# H3_CPU_02.net
KiCad netlist of a schematic drawn in Altium Designer
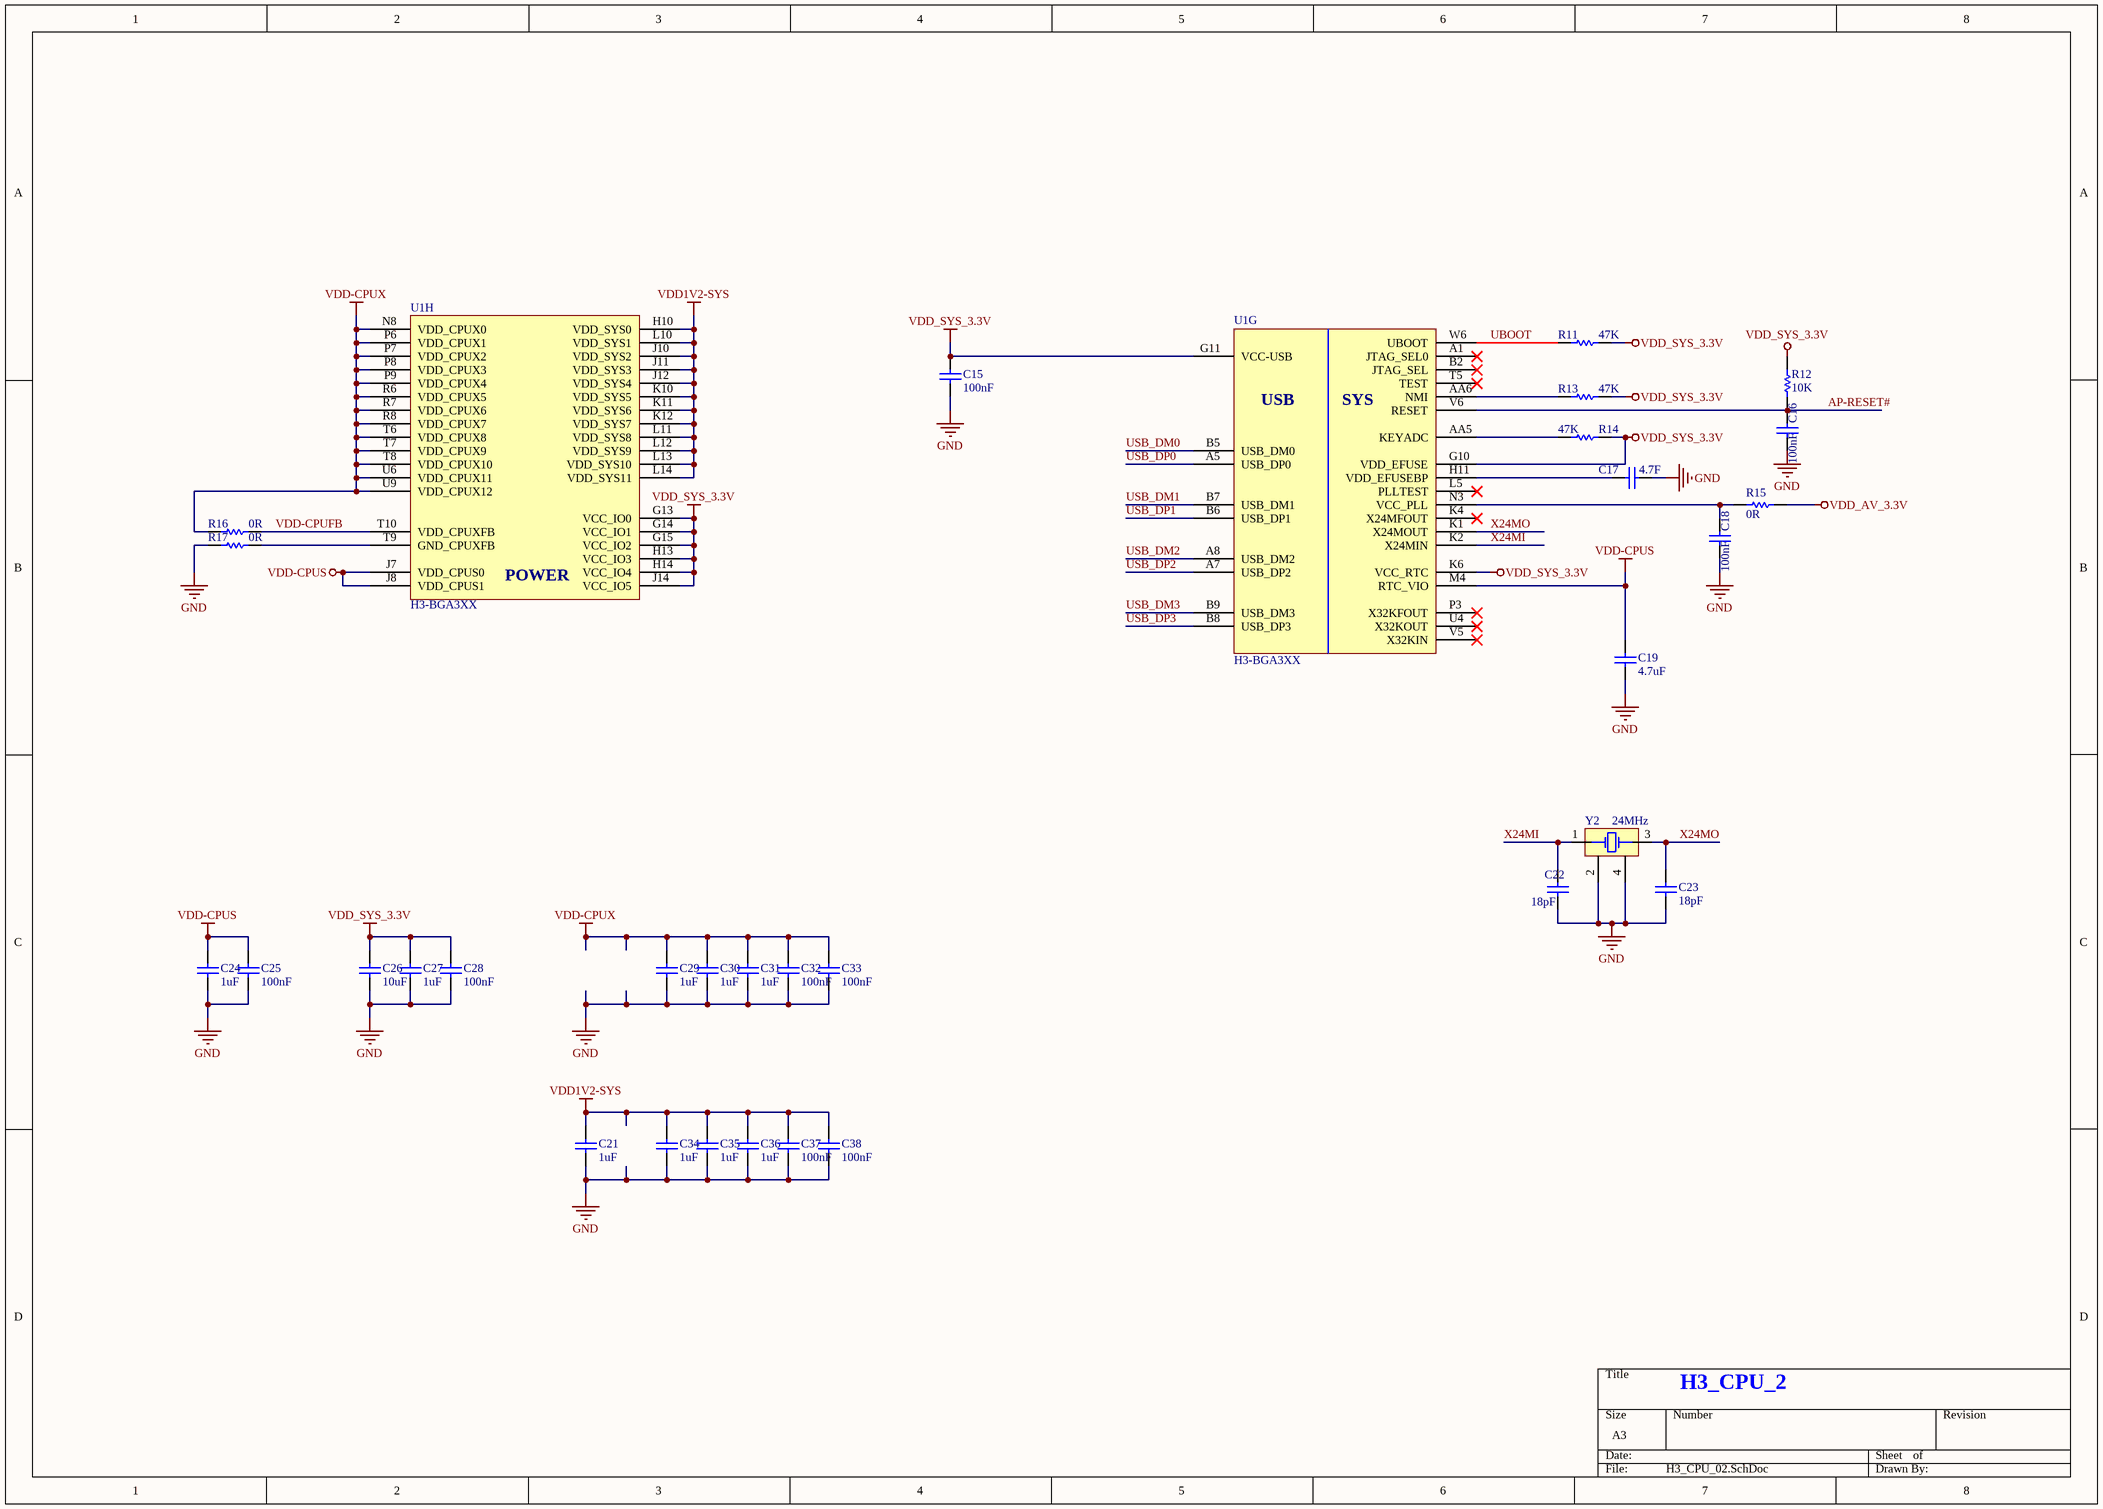
[diagram p0: H3_CPU_02.SchDoc]

(export (version "E")
  (design (tool "Eeschema 10.0.6"))
  (components
    (comp (ref "C15")
      (value "100nF")
      (footprint "H3_Core:C0402")
      (description "电容")
      (fields (field (name "PUBLISHER") "Altium Limited"))
      (libsource (lib "Devices") (part "C0402"))
    )
    (comp (ref "C16")
      (value "100nF")
      (footprint "H3_Core:C0402")
      (description "电容")
      (fields (field (name "PUBLISHER") "Altium Limited"))
      (libsource (lib "Devices") (part "C0402"))
    )
    (comp (ref "C17")
      (value "4.7F")
      (footprint "H3_Core:C0402")
      (description "电容")
      (fields (field (name "PUBLISHER") "Altium Limited"))
      (libsource (lib "Devices") (part "C0402"))
    )
    (comp (ref "C18")
      (value "100nF")
      (footprint "H3_Core:C0402")
      (description "电容")
      (fields (field (name "PUBLISHER") "Altium Limited"))
      (libsource (lib "Devices") (part "C0402"))
    )
    (comp (ref "C19")
      (value "4.7uF")
      (footprint "H3_Core:C0402")
      (description "电容")
      (fields (field (name "PUBLISHER") "Altium Limited"))
      (libsource (lib "Devices") (part "C0402"))
    )
    (comp (ref "C21")
      (value "1uF")
      (footprint "H3_Core:C0402")
      (description "电容")
      (fields (field (name "PUBLISHER") "Altium Limited"))
      (libsource (lib "Devices") (part "C0402"))
    )
    (comp (ref "C22")
      (value "18pF")
      (footprint "H3_Core:C0402")
      (description "电容")
      (fields (field (name "PUBLISHER") "Altium Limited"))
      (libsource (lib "Devices") (part "C0402"))
    )
    (comp (ref "C23")
      (value "18pF")
      (footprint "H3_Core:C0402")
      (description "电容")
      (fields (field (name "PUBLISHER") "Altium Limited"))
      (libsource (lib "Devices") (part "C0402"))
    )
    (comp (ref "C24")
      (value "1uF")
      (footprint "H3_Core:C0402")
      (description "电容")
      (fields (field (name "PUBLISHER") "Altium Limited"))
      (libsource (lib "Devices") (part "C0402"))
    )
    (comp (ref "C25")
      (value "100nF")
      (footprint "H3_Core:C0402")
      (description "电容")
      (fields (field (name "PUBLISHER") "Altium Limited"))
      (libsource (lib "Devices") (part "C0402"))
    )
    (comp (ref "C26")
      (value "10uF")
      (footprint "H3_Core:C0603")
      (description "电容")
      (fields (field (name "PUBLISHER") "Altium Limited"))
      (libsource (lib "Devices") (part "C0603"))
    )
    (comp (ref "C27")
      (value "1uF")
      (footprint "H3_Core:C0402")
      (description "电容")
      (fields (field (name "PUBLISHER") "Altium Limited"))
      (libsource (lib "Devices") (part "C0402"))
    )
    (comp (ref "C28")
      (value "100nF")
      (footprint "H3_Core:C0402")
      (description "电容")
      (fields (field (name "PUBLISHER") "Altium Limited"))
      (libsource (lib "Devices") (part "C0402"))
    )
    (comp (ref "C29")
      (value "1uF")
      (footprint "H3_Core:C0402")
      (description "电容")
      (fields (field (name "PUBLISHER") "Altium Limited"))
      (libsource (lib "Devices") (part "C0402"))
    )
    (comp (ref "C30")
      (value "1uF")
      (footprint "H3_Core:C0402")
      (description "电容")
      (fields (field (name "PUBLISHER") "Altium Limited"))
      (libsource (lib "Devices") (part "C0402"))
    )
    (comp (ref "C31")
      (value "1uF")
      (footprint "H3_Core:C0402")
      (description "电容")
      (fields (field (name "PUBLISHER") "Altium Limited"))
      (libsource (lib "Devices") (part "C0402"))
    )
    (comp (ref "C32")
      (value "100nF")
      (footprint "H3_Core:C0402")
      (description "电容")
      (fields (field (name "PUBLISHER") "Altium Limited"))
      (libsource (lib "Devices") (part "C0402"))
    )
    (comp (ref "C33")
      (value "100nF")
      (footprint "H3_Core:C0402")
      (description "电容")
      (fields (field (name "PUBLISHER") "Altium Limited"))
      (libsource (lib "Devices") (part "C0402"))
    )
    (comp (ref "C34")
      (value "1uF")
      (footprint "H3_Core:C0402")
      (description "电容")
      (fields (field (name "PUBLISHER") "Altium Limited"))
      (libsource (lib "Devices") (part "C0402"))
    )
    (comp (ref "C35")
      (value "1uF")
      (footprint "H3_Core:C0402")
      (description "电容")
      (fields (field (name "PUBLISHER") "Altium Limited"))
      (libsource (lib "Devices") (part "C0402"))
    )
    (comp (ref "C36")
      (value "1uF")
      (footprint "H3_Core:C0402")
      (description "电容")
      (fields (field (name "PUBLISHER") "Altium Limited"))
      (libsource (lib "Devices") (part "C0402"))
    )
    (comp (ref "C37")
      (value "100nF")
      (footprint "H3_Core:C0402")
      (description "电容")
      (fields (field (name "PUBLISHER") "Altium Limited"))
      (libsource (lib "Devices") (part "C0402"))
    )
    (comp (ref "C38")
      (value "100nF")
      (footprint "H3_Core:C0402")
      (description "电容")
      (fields (field (name "PUBLISHER") "Altium Limited"))
      (libsource (lib "Devices") (part "C0402"))
    )
    (comp (ref "R11")
      (value "47K")
      (footprint "H3_Core:R0402")
      (description "电阻")
      (fields (field (name "PUBLISHER") "Altium Limited"))
      (libsource (lib "Devices") (part "RES0402"))
    )
    (comp (ref "R12")
      (value "10K")
      (footprint "H3_Core:R0402")
      (description "电阻")
      (fields (field (name "PUBLISHER") "Altium Limited"))
      (libsource (lib "Devices") (part "RES0402"))
    )
    (comp (ref "R13")
      (value "47K")
      (footprint "H3_Core:R0402")
      (description "电阻")
      (fields (field (name "PUBLISHER") "Altium Limited"))
      (libsource (lib "Devices") (part "RES0402"))
    )
    (comp (ref "R14")
      (value "47K")
      (footprint "H3_Core:R0402")
      (description "电阻")
      (fields (field (name "PUBLISHER") "Altium Limited"))
      (libsource (lib "Devices") (part "RES0402"))
    )
    (comp (ref "R15")
      (value "0R")
      (footprint "H3_Core:R0402")
      (description "电阻")
      (fields (field (name "PUBLISHER") "Altium Limited"))
      (libsource (lib "Devices") (part "RES0402"))
    )
    (comp (ref "R16")
      (value "0R")
      (footprint "H3_Core:R0402")
      (description "电阻")
      (fields (field (name "PUBLISHER") "Altium Limited"))
      (libsource (lib "Devices") (part "RES0402"))
    )
    (comp (ref "R17")
      (value "0R")
      (footprint "H3_Core:R0402")
      (description "电阻")
      (fields (field (name "PUBLISHER") "Altium Limited"))
      (libsource (lib "Devices") (part "RES0402"))
    )
    (comp (ref "U1") (value "H3-BGA3XX") (footprint "BGA-H3-347") (libsource (lib "IC") (part "H3-BGA3XX")))
    (comp (ref "Y2")
      (value "24MHz")
      (footprint "H3_Core:X-TSX-3225")
      (description "Crystal Oscillator")
      (fields (field (name "PUBLISHER") "Altium Limited"))
      (libsource (lib "Devices") (part "XTAL_1"))
    )
  )
  (nets
    (net (code "1") (name "/AP-RESET#") (class "Default")
      (node (ref "C16") (pin "2") (pinfunction "2_2") (pintype "passive"))
      (node (ref "R12") (pin "1") (pinfunction "1_1") (pintype "passive"))
      (node (ref "U1") (pin "V6") (pinfunction "RESET_V6") (pintype "passive"))
    )
    (net (code "2") (name "/UBOOT") (class "Default")
      (node (ref "R11") (pin "2") (pinfunction "2_2") (pintype "passive"))
      (node (ref "U1") (pin "W6") (pinfunction "UBOOT_W6") (pintype "passive"))
    )
    (net (code "3") (name "/USB_DM0") (class "Default")
      (node (ref "U1") (pin "B5") (pinfunction "USB_DM0_B5") (pintype "passive"))
    )
    (net (code "4") (name "/USB_DM1") (class "Default")
      (node (ref "U1") (pin "B7") (pinfunction "USB_DM1_B7") (pintype "passive"))
    )
    (net (code "5") (name "/USB_DM2") (class "Default")
      (node (ref "U1") (pin "A8") (pinfunction "USB_DM2_A8") (pintype "passive"))
    )
    (net (code "6") (name "/USB_DM3") (class "Default")
      (node (ref "U1") (pin "B9") (pinfunction "USB_DM3_B9") (pintype "passive"))
    )
    (net (code "7") (name "/USB_DP0") (class "Default")
      (node (ref "U1") (pin "A5") (pinfunction "USB_DP0_A5") (pintype "passive"))
    )
    (net (code "8") (name "/USB_DP1") (class "Default")
      (node (ref "U1") (pin "B6") (pinfunction "USB_DP1_B6") (pintype "passive"))
    )
    (net (code "9") (name "/USB_DP2") (class "Default")
      (node (ref "U1") (pin "A7") (pinfunction "USB_DP2_A7") (pintype "passive"))
    )
    (net (code "10") (name "/USB_DP3") (class "Default")
      (node (ref "U1") (pin "B8") (pinfunction "USB_DP3_B8") (pintype "passive"))
    )
    (net (code "11") (name "/VDD-CPUFB") (class "Default")
      (node (ref "R16") (pin "1") (pinfunction "1_1") (pintype "passive"))
      (node (ref "U1") (pin "T10") (pinfunction "VDD_CPUXFB_T10") (pintype "passive"))
    )
    (net (code "12") (name "/X24MI") (class "Default")
      (node (ref "C22") (pin "2") (pinfunction "2_2") (pintype "passive"))
      (node (ref "U1") (pin "K2") (pinfunction "X24MIN_K2") (pintype "passive"))
      (node (ref "Y2") (pin "1") (pinfunction "1_1") (pintype "passive"))
    )
    (net (code "13") (name "/X24MO") (class "Default")
      (node (ref "C23") (pin "2") (pinfunction "2_2") (pintype "passive"))
      (node (ref "U1") (pin "K1") (pinfunction "X24MOUT_K1") (pintype "passive"))
      (node (ref "Y2") (pin "3") (pinfunction "3_3") (pintype "passive"))
    )
    (net (code "14") (name "GND") (class "Default")
      (node (ref "C15") (pin "1") (pinfunction "1_1") (pintype "passive"))
      (node (ref "C16") (pin "1") (pinfunction "1_1") (pintype "passive"))
      (node (ref "C17") (pin "1") (pinfunction "1_1") (pintype "passive"))
      (node (ref "C18") (pin "1") (pinfunction "1_1") (pintype "passive"))
      (node (ref "C19") (pin "1") (pinfunction "1_1") (pintype "passive"))
      (node (ref "C21") (pin "1") (pinfunction "1_1") (pintype "passive"))
      (node (ref "C22") (pin "1") (pinfunction "1_1") (pintype "passive"))
      (node (ref "C23") (pin "1") (pinfunction "1_1") (pintype "passive"))
      (node (ref "C24") (pin "1") (pinfunction "1_1") (pintype "passive"))
      (node (ref "C25") (pin "1") (pinfunction "1_1") (pintype "passive"))
      (node (ref "C26") (pin "1") (pinfunction "1_1") (pintype "passive"))
      (node (ref "C27") (pin "1") (pinfunction "1_1") (pintype "passive"))
      (node (ref "C28") (pin "1") (pinfunction "1_1") (pintype "passive"))
      (node (ref "C29") (pin "1") (pinfunction "1_1") (pintype "passive"))
      (node (ref "C30") (pin "1") (pinfunction "1_1") (pintype "passive"))
      (node (ref "C31") (pin "1") (pinfunction "1_1") (pintype "passive"))
      (node (ref "C32") (pin "1") (pinfunction "1_1") (pintype "passive"))
      (node (ref "C33") (pin "1") (pinfunction "1_1") (pintype "passive"))
      (node (ref "C34") (pin "1") (pinfunction "1_1") (pintype "passive"))
      (node (ref "C35") (pin "1") (pinfunction "1_1") (pintype "passive"))
      (node (ref "C36") (pin "1") (pinfunction "1_1") (pintype "passive"))
      (node (ref "C37") (pin "1") (pinfunction "1_1") (pintype "passive"))
      (node (ref "C38") (pin "1") (pinfunction "1_1") (pintype "passive"))
      (node (ref "R17") (pin "1") (pinfunction "1_1") (pintype "passive"))
      (node (ref "Y2") (pin "2") (pinfunction "2_2") (pintype "passive"))
      (node (ref "Y2") (pin "4") (pinfunction "4_4") (pintype "passive"))
    )
    (net (code "15") (name "Net-(U1G-KEYADC)") (class "Default")
      (node (ref "R14") (pin "1") (pinfunction "1_1") (pintype "passive"))
      (node (ref "U1") (pin "AA5") (pinfunction "KEYADC_AA5") (pintype "passive"))
    )
    (net (code "16") (name "Net-(U1G-NMI)") (class "Default")
      (node (ref "R13") (pin "1") (pinfunction "1_1") (pintype "passive"))
      (node (ref "U1") (pin "AA6") (pinfunction "NMI_AA6") (pintype "passive"))
    )
    (net (code "17") (name "Net-(U1G-VCC_PLL)") (class "Default")
      (node (ref "C18") (pin "2") (pinfunction "2_2") (pintype "passive"))
      (node (ref "R15") (pin "2") (pinfunction "2_2") (pintype "passive"))
      (node (ref "U1") (pin "N3") (pinfunction "VCC_PLL_N3") (pintype "passive"))
    )
    (net (code "18") (name "Net-(U1G-VDD_EFUSEBP)") (class "Default")
      (node (ref "C17") (pin "2") (pinfunction "2_2") (pintype "passive"))
      (node (ref "U1") (pin "H11") (pinfunction "VDD_EFUSEBP_H11") (pintype "passive"))
    )
    (net (code "19") (name "Net-(U1H-GND_CPUXFB)") (class "Default")
      (node (ref "R17") (pin "2") (pinfunction "2_2") (pintype "passive"))
      (node (ref "U1") (pin "T9") (pinfunction "GND_CPUXFB_T9") (pintype "passive"))
    )
    (net (code "20") (name "VDD-CPUS") (class "Default")
      (node (ref "C19") (pin "2") (pinfunction "2_2") (pintype "passive"))
      (node (ref "C24") (pin "2") (pinfunction "2_2") (pintype "passive"))
      (node (ref "C25") (pin "2") (pinfunction "2_2") (pintype "passive"))
      (node (ref "U1") (pin "J7") (pinfunction "VDD_CPUS0_J7") (pintype "passive"))
      (node (ref "U1") (pin "J8") (pinfunction "VDD_CPUS1_J8") (pintype "passive"))
      (node (ref "U1") (pin "M4") (pinfunction "RTC_VIO_M4") (pintype "passive"))
    )
    (net (code "21") (name "VDD-CPUX") (class "Default")
      (node (ref "C29") (pin "2") (pinfunction "2_2") (pintype "passive"))
      (node (ref "C30") (pin "2") (pinfunction "2_2") (pintype "passive"))
      (node (ref "C31") (pin "2") (pinfunction "2_2") (pintype "passive"))
      (node (ref "C32") (pin "2") (pinfunction "2_2") (pintype "passive"))
      (node (ref "C33") (pin "2") (pinfunction "2_2") (pintype "passive"))
      (node (ref "R16") (pin "2") (pinfunction "2_2") (pintype "passive"))
      (node (ref "U1") (pin "N8") (pinfunction "VDD_CPUX0_N8") (pintype "passive"))
      (node (ref "U1") (pin "P6") (pinfunction "VDD_CPUX1_P6") (pintype "passive"))
      (node (ref "U1") (pin "P7") (pinfunction "VDD_CPUX2_P7") (pintype "passive"))
      (node (ref "U1") (pin "P8") (pinfunction "VDD_CPUX3_P8") (pintype "passive"))
      (node (ref "U1") (pin "P9") (pinfunction "VDD_CPUX4_P9") (pintype "passive"))
      (node (ref "U1") (pin "R6") (pinfunction "VDD_CPUX5_R6") (pintype "passive"))
      (node (ref "U1") (pin "R7") (pinfunction "VDD_CPUX6_R7") (pintype "passive"))
      (node (ref "U1") (pin "R8") (pinfunction "VDD_CPUX7_R8") (pintype "passive"))
      (node (ref "U1") (pin "T6") (pinfunction "VDD_CPUX8_T6") (pintype "passive"))
      (node (ref "U1") (pin "T7") (pinfunction "VDD_CPUX9_T7") (pintype "passive"))
      (node (ref "U1") (pin "T8") (pinfunction "VDD_CPUX10_T8") (pintype "passive"))
      (node (ref "U1") (pin "U6") (pinfunction "VDD_CPUX11_U6") (pintype "passive"))
      (node (ref "U1") (pin "U9") (pinfunction "VDD_CPUX12_U9") (pintype "passive"))
    )
    (net (code "22") (name "VDD1V2-SYS") (class "Default")
      (node (ref "C21") (pin "2") (pinfunction "2_2") (pintype "passive"))
      (node (ref "C34") (pin "2") (pinfunction "2_2") (pintype "passive"))
      (node (ref "C35") (pin "2") (pinfunction "2_2") (pintype "passive"))
      (node (ref "C36") (pin "2") (pinfunction "2_2") (pintype "passive"))
      (node (ref "C37") (pin "2") (pinfunction "2_2") (pintype "passive"))
      (node (ref "C38") (pin "2") (pinfunction "2_2") (pintype "passive"))
      (node (ref "U1") (pin "H10") (pinfunction "VDD_SYS0_H10") (pintype "passive"))
      (node (ref "U1") (pin "J10") (pinfunction "VDD_SYS2_J10") (pintype "passive"))
      (node (ref "U1") (pin "J11") (pinfunction "VDD_SYS3_J11") (pintype "passive"))
      (node (ref "U1") (pin "J12") (pinfunction "VDD_SYS4_J12") (pintype "passive"))
      (node (ref "U1") (pin "K10") (pinfunction "VDD_SYS5_K10") (pintype "passive"))
      (node (ref "U1") (pin "K11") (pinfunction "VDD_SYS6_K11") (pintype "passive"))
      (node (ref "U1") (pin "K12") (pinfunction "VDD_SYS7_K12") (pintype "passive"))
      (node (ref "U1") (pin "L10") (pinfunction "VDD_SYS1_L10") (pintype "passive"))
      (node (ref "U1") (pin "L11") (pinfunction "VDD_SYS8_L11") (pintype "passive"))
      (node (ref "U1") (pin "L12") (pinfunction "VDD_SYS9_L12") (pintype "passive"))
      (node (ref "U1") (pin "L13") (pinfunction "VDD_SYS10_L13") (pintype "passive"))
      (node (ref "U1") (pin "L14") (pinfunction "VDD_SYS11_L14") (pintype "passive"))
    )
    (net (code "23") (name "VDD_AV_3.3V") (class "Default")
      (node (ref "R15") (pin "1") (pinfunction "1_1") (pintype "passive"))
    )
    (net (code "24") (name "VDD_SYS_3.3V") (class "Default")
      (node (ref "C15") (pin "2") (pinfunction "2_2") (pintype "passive"))
      (node (ref "C26") (pin "2") (pinfunction "2_2") (pintype "passive"))
      (node (ref "C27") (pin "2") (pinfunction "2_2") (pintype "passive"))
      (node (ref "C28") (pin "2") (pinfunction "2_2") (pintype "passive"))
      (node (ref "R11") (pin "1") (pinfunction "1_1") (pintype "passive"))
      (node (ref "R12") (pin "2") (pinfunction "2_2") (pintype "passive"))
      (node (ref "R13") (pin "2") (pinfunction "2_2") (pintype "passive"))
      (node (ref "R14") (pin "2") (pinfunction "2_2") (pintype "passive"))
      (node (ref "U1") (pin "G10") (pinfunction "VDD_EFUSE_G10") (pintype "passive"))
      (node (ref "U1") (pin "G11") (pinfunction "VCC-USB_G11") (pintype "passive"))
      (node (ref "U1") (pin "G13") (pinfunction "VCC_IO0_G13") (pintype "passive"))
      (node (ref "U1") (pin "G14") (pinfunction "VCC_IO1_G14") (pintype "passive"))
      (node (ref "U1") (pin "G15") (pinfunction "VCC_IO2_G15") (pintype "passive"))
      (node (ref "U1") (pin "H13") (pinfunction "VCC_IO3_H13") (pintype "passive"))
      (node (ref "U1") (pin "H14") (pinfunction "VCC_IO4_H14") (pintype "passive"))
      (node (ref "U1") (pin "J14") (pinfunction "VCC_IO5_J14") (pintype "passive"))
      (node (ref "U1") (pin "K6") (pinfunction "VCC_RTC_K6") (pintype "passive"))
    )
    (net (code "25") (name "unconnected-(U1G-JTAG_SEL-PadB2)") (class "Default")
      (node (ref "U1") (pin "B2") (pinfunction "JTAG_SEL_B2") (pintype "passive+no_connect"))
    )
    (net (code "26") (name "unconnected-(U1G-JTAG_SEL0-PadA1)") (class "Default")
      (node (ref "U1") (pin "A1") (pinfunction "JTAG_SEL0_A1") (pintype "passive+no_connect"))
    )
    (net (code "27") (name "unconnected-(U1G-PLLTEST-PadL5)") (class "Default")
      (node (ref "U1") (pin "L5") (pinfunction "PLLTEST_L5") (pintype "passive+no_connect"))
    )
    (net (code "28") (name "unconnected-(U1G-TEST-PadT5)") (class "Default")
      (node (ref "U1") (pin "T5") (pinfunction "TEST_T5") (pintype "passive+no_connect"))
    )
    (net (code "29") (name "unconnected-(U1G-X24MFOUT-PadK4)") (class "Default")
      (node (ref "U1") (pin "K4") (pinfunction "X24MFOUT_K4") (pintype "passive+no_connect"))
    )
    (net (code "30") (name "unconnected-(U1G-X32KFOUT-PadP3)") (class "Default")
      (node (ref "U1") (pin "P3") (pinfunction "X32KFOUT_P3") (pintype "passive+no_connect"))
    )
    (net (code "31") (name "unconnected-(U1G-X32KIN-PadV5)") (class "Default")
      (node (ref "U1") (pin "V5") (pinfunction "X32KIN_V5") (pintype "passive+no_connect"))
    )
    (net (code "32") (name "unconnected-(U1G-X32KOUT-PadU4)") (class "Default")
      (node (ref "U1") (pin "U4") (pinfunction "X32KOUT_U4") (pintype "passive+no_connect"))
    )
  )
)
